# bt-audio-receiver.net
KiCad netlist of a schematic drawn in EAGLE
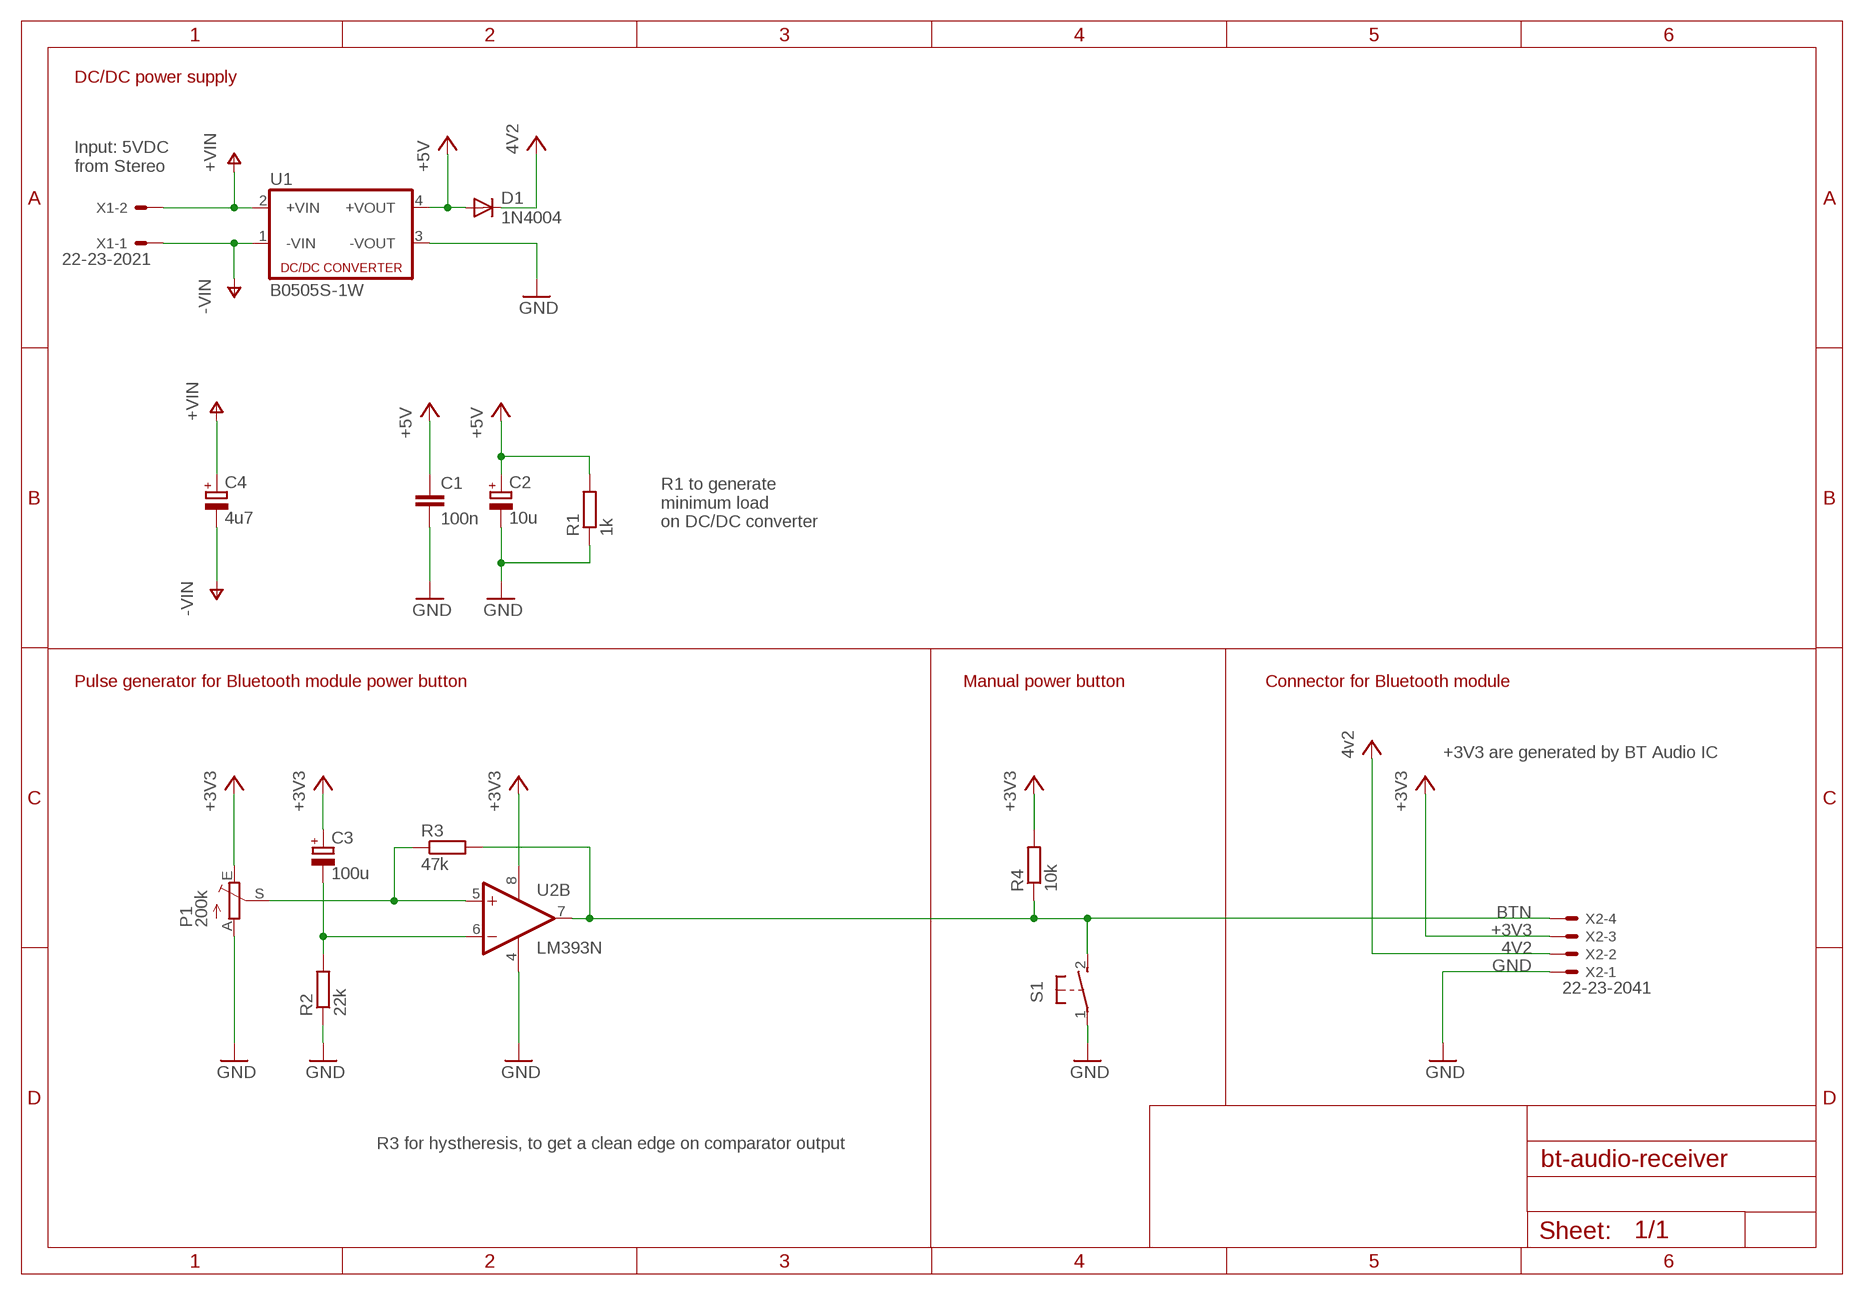
[diagram p0: schematic, sheet 1]

(export (version "E")
  (design (tool "Eeschema 10.0.6"))
  (components
    (comp (ref "C1")
      (value "100n")
      (footprint "eagle-import:C025-025X050")
      (libsource (lib "eagle-import") (part "C-EU025-025X050"))
    )
    (comp (ref "C2")
      (value "10u")
      (footprint "eagle-import:E2-4")
      (libsource (lib "eagle-import") (part "CPOL-EUE2-4"))
    )
    (comp (ref "C3")
      (value "100u")
      (footprint "eagle-import:E2,5-5")
      (libsource (lib "eagle-import") (part "CPOL-EUE2.5-5"))
    )
    (comp (ref "C4")
      (value "4u7")
      (footprint "eagle-import:E2-4")
      (libsource (lib "eagle-import") (part "CPOL-EUE2-4"))
    )
    (comp (ref "D1")
      (value "1N4004")
      (footprint "eagle-import:DO41-10")
      (libsource (lib "eagle-import") (part "1N4004"))
    )
    (comp (ref "P1")
      (value "200k")
      (footprint "eagle-import:B25P")
      (libsource (lib "eagle-import") (part "TRIM_EU-B25P"))
    )
    (comp (ref "R1")
      (value "1k")
      (footprint "eagle-import:0204V")
      (libsource (lib "eagle-import") (part "R-EU_0204/2V"))
    )
    (comp (ref "R2")
      (value "22k")
      (footprint "eagle-import:0204_7")
      (libsource (lib "eagle-import") (part "R-EU_0204/7"))
    )
    (comp (ref "R3")
      (value "47k")
      (footprint "eagle-import:0204_5")
      (libsource (lib "eagle-import") (part "R-EU_0204/5"))
    )
    (comp (ref "R4")
      (value "10k")
      (footprint "eagle-import:0204V")
      (libsource (lib "eagle-import") (part "R-EU_0204/2V"))
    )
    (comp (ref "S1")
      (value "DTS-3")
      (footprint "eagle-import:DTS-3")
      (libsource (lib "eagle-import") (part "DTS-3"))
    )
    (comp (ref "U1")
      (value "B0505S-1W")
      (footprint "eagle-import:4SIL")
      (libsource (lib "eagle-import") (part "VA-?S10505"))
    )
    (comp (ref "U2")
      (value "LM393N")
      (footprint "eagle-import:DIL08")
      (libsource (lib "eagle-import") (part "LM393N"))
    )
    (comp (ref "X1")
      (value "22-23-2021")
      (footprint "eagle-import:22-23-2021")
      (fields (field (name "MF") "MOLEX"))
      (libsource (lib "eagle-import") (part "22-23-2021"))
    )
    (comp (ref "X2")
      (value "22-23-2041")
      (footprint "eagle-import:22-23-2041")
      (fields (field (name "MF") "MOLEX"))
      (libsource (lib "eagle-import") (part "22-23-2041"))
    )
  )
  (nets
    (net (code "1") (name "+3V3") (class "Default")
      (node (ref "C3") (pin "+") (pinfunction "+_+") (pintype "passive"))
      (node (ref "P1") (pin "E") (pinfunction "E_E") (pintype "passive"))
      (node (ref "R4") (pin "2") (pinfunction "2_2") (pintype "passive"))
      (node (ref "U2") (pin "8") (pinfunction "V+_8") (pintype "power_in"))
      (node (ref "X2") (pin "3") (pinfunction "S_3") (pintype "passive"))
    )
    (net (code "2") (name "+5V") (class "Default")
      (node (ref "C1") (pin "1") (pinfunction "1_1") (pintype "passive"))
      (node (ref "C2") (pin "+") (pinfunction "+_+") (pintype "passive"))
      (node (ref "D1") (pin "A") (pinfunction "A_A") (pintype "passive"))
      (node (ref "R1") (pin "2") (pinfunction "2_2") (pintype "passive"))
      (node (ref "U1") (pin "4") (pinfunction "+VOUT_4") (pintype "passive"))
    )
    (net (code "3") (name "+VIN") (class "Default")
      (node (ref "C4") (pin "+") (pinfunction "+_+") (pintype "passive"))
      (node (ref "U1") (pin "2") (pinfunction "+VIN_2") (pintype "passive"))
      (node (ref "X1") (pin "2") (pinfunction "S_2") (pintype "passive"))
    )
    (net (code "4") (name "-VIN") (class "Default")
      (node (ref "C4") (pin "-") (pinfunction "-_-") (pintype "passive"))
      (node (ref "U1") (pin "1") (pinfunction "-VIN_1") (pintype "passive"))
      (node (ref "X1") (pin "1") (pinfunction "S_1") (pintype "passive"))
    )
    (net (code "5") (name "/BTN") (class "Default")
      (node (ref "R3") (pin "2") (pinfunction "2_2") (pintype "passive"))
      (node (ref "R4") (pin "1") (pinfunction "1_1") (pintype "passive"))
      (node (ref "S1") (pin "2") (pinfunction "2_2") (pintype "passive"))
      (node (ref "U2") (pin "7") (pinfunction "OUT_7") (pintype "output"))
      (node (ref "X2") (pin "4") (pinfunction "S_4") (pintype "passive"))
    )
    (net (code "6") (name "4V2") (class "Default")
      (node (ref "D1") (pin "C") (pinfunction "C_C") (pintype "passive"))
      (node (ref "X2") (pin "2") (pinfunction "S_2") (pintype "passive"))
    )
    (net (code "7") (name "GND") (class "Default")
      (node (ref "C1") (pin "2") (pinfunction "2_2") (pintype "passive"))
      (node (ref "C2") (pin "-") (pinfunction "-_-") (pintype "passive"))
      (node (ref "P1") (pin "A") (pinfunction "A_A") (pintype "passive"))
      (node (ref "R1") (pin "1") (pinfunction "1_1") (pintype "passive"))
      (node (ref "R2") (pin "1") (pinfunction "1_1") (pintype "passive"))
      (node (ref "S1") (pin "1") (pinfunction "1_1") (pintype "passive"))
      (node (ref "U1") (pin "3") (pinfunction "-VOUT_3") (pintype "passive"))
      (node (ref "U2") (pin "4") (pinfunction "V-_4") (pintype "power_in"))
      (node (ref "X2") (pin "1") (pinfunction "S_1") (pintype "passive"))
    )
    (net (code "8") (name "Net-(U2B-+IN)") (class "Default")
      (node (ref "P1") (pin "S") (pinfunction "S_S") (pintype "passive"))
      (node (ref "R3") (pin "1") (pinfunction "1_1") (pintype "passive"))
      (node (ref "U2") (pin "5") (pinfunction "+IN_5") (pintype "input"))
    )
    (net (code "9") (name "Net-(U2B--IN)") (class "Default")
      (node (ref "C3") (pin "-") (pinfunction "-_-") (pintype "passive"))
      (node (ref "R2") (pin "2") (pinfunction "2_2") (pintype "passive"))
      (node (ref "U2") (pin "6") (pinfunction "-IN_6") (pintype "input"))
    )
  )
)
